# lcmeter.net
KiCad netlist of a schematic drawn in EAGLE
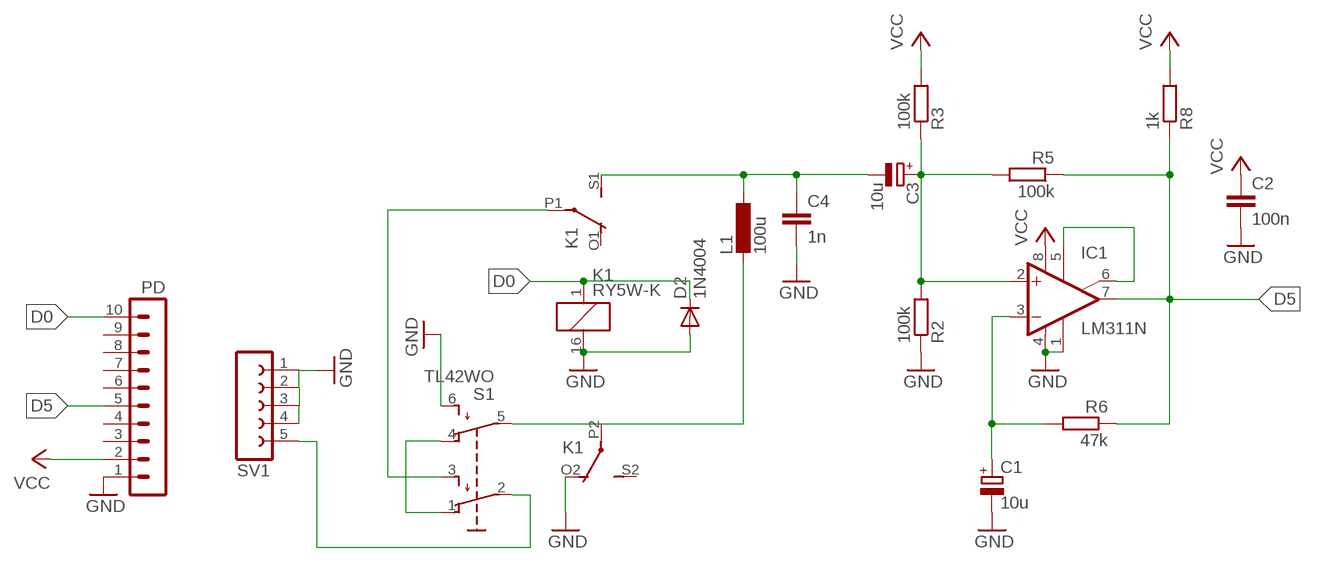
[diagram p0: schematic, sheet 1]

(export (version "E")
  (design (tool "Eeschema 10.0.6"))
  (components
    (comp (ref "C1")
      (value "10u")
      (footprint "eagle-import:E2,5-6")
      (libsource (lib "eagle-import") (part "CPOL-EUE2.5-6"))
    )
    (comp (ref "C2")
      (value "100n")
      (footprint "eagle-import:C025-024X044")
      (libsource (lib "eagle-import") (part "C-EU025-024X044"))
    )
    (comp (ref "C3")
      (value "10u")
      (footprint "eagle-import:TT5D7")
      (libsource (lib "eagle-import") (part "CPOL-EUTT5D7"))
    )
    (comp (ref "C4")
      (value "1n")
      (footprint "eagle-import:C050-025X075")
      (libsource (lib "eagle-import") (part "C-EU050-025X075"))
    )
    (comp (ref "D2")
      (value "1N4004")
      (footprint "eagle-import:DO35-7")
      (libsource (lib "eagle-import") (part "1N4148DO35-7"))
    )
    (comp (ref "IC1")
      (value "LM311N")
      (footprint "eagle-import:DIL08")
      (libsource (lib "eagle-import") (part "LM311N"))
    )
    (comp (ref "K1")
      (value "RY5W-K")
      (footprint "eagle-import:351")
      (libsource (lib "eagle-import") (part "351"))
    )
    (comp (ref "L1")
      (value "100u")
      (footprint "eagle-import:0204_7")
      (libsource (lib "eagle-import") (part "L-EU0204/7"))
    )
    (comp (ref "PD")
      (value "MA10-1W")
      (footprint "eagle-import:MA10-1W")
      (libsource (lib "eagle-import") (part "MA10-1W"))
    )
    (comp (ref "R2")
      (value "100k")
      (footprint "eagle-import:0207_10")
      (libsource (lib "eagle-import") (part "R-EU_0207/10"))
    )
    (comp (ref "R3")
      (value "100k")
      (footprint "eagle-import:0204_7")
      (libsource (lib "eagle-import") (part "R-EU_0204/7"))
    )
    (comp (ref "R5")
      (value "100k")
      (footprint "eagle-import:0204_7")
      (libsource (lib "eagle-import") (part "R-EU_0204/7"))
    )
    (comp (ref "R6")
      (value "47k")
      (footprint "eagle-import:0204_5")
      (libsource (lib "eagle-import") (part "R-EU_0204/5"))
    )
    (comp (ref "R8")
      (value "1k")
      (footprint "eagle-import:0204_7")
      (libsource (lib "eagle-import") (part "R-EU_0204/7"))
    )
    (comp (ref "S1")
      (value "TL42WO")
      (footprint "eagle-import:TL4XWO")
      (libsource (lib "eagle-import") (part "TL42WO"))
    )
    (comp (ref "SV1")
      (value "FE05W")
      (footprint "eagle-import:FE05W")
      (libsource (lib "eagle-import") (part "FE05W"))
    )
  )
  (nets
    (net (code "1") (name "D0") (class "Default")
      (node (ref "D2") (pin "C") (pinfunction "C_C") (pintype "passive"))
      (node (ref "K1") (pin "1") (pinfunction "1_1") (pintype "passive"))
      (node (ref "PD") (pin "10") (pinfunction "10_10") (pintype "passive"))
    )
    (net (code "2") (name "D5") (class "Default")
      (node (ref "IC1") (pin "7") (pinfunction "OUT_7") (pintype "output"))
      (node (ref "PD") (pin "5") (pinfunction "5_5") (pintype "passive"))
      (node (ref "R5") (pin "1") (pinfunction "1_1") (pintype "passive"))
      (node (ref "R6") (pin "1") (pinfunction "1_1") (pintype "passive"))
      (node (ref "R8") (pin "1") (pinfunction "1_1") (pintype "passive"))
    )
    (net (code "3") (name "GND") (class "Default")
      (node (ref "C1") (pin "-") (pinfunction "-_-") (pintype "passive"))
      (node (ref "C2") (pin "2") (pinfunction "2_2") (pintype "passive"))
      (node (ref "C4") (pin "2") (pinfunction "2_2") (pintype "passive"))
      (node (ref "D2") (pin "A") (pinfunction "A_A") (pintype "passive"))
      (node (ref "IC1") (pin "1") (pinfunction "GND_1") (pintype "passive"))
      (node (ref "IC1") (pin "4") (pinfunction "V-_4") (pintype "power_in"))
      (node (ref "K1") (pin "16") (pinfunction "2_16") (pintype "passive"))
      (node (ref "K1") (pin "O2") (pinfunction "O_O2") (pintype "passive"))
      (node (ref "PD") (pin "1") (pinfunction "1_1") (pintype "passive"))
      (node (ref "R2") (pin "1") (pinfunction "1_1") (pintype "passive"))
      (node (ref "S1") (pin "6") (pinfunction "S1_6") (pintype "passive"))
      (node (ref "SV1") (pin "1") (pinfunction "1_1") (pintype "passive"))
      (node (ref "SV1") (pin "2") (pinfunction "2_2") (pintype "passive"))
      (node (ref "SV1") (pin "3") (pinfunction "3_3") (pintype "passive"))
      (node (ref "SV1") (pin "4") (pinfunction "4_4") (pintype "passive"))
    )
    (net (code "4") (name "Net-(IC1-+IN)") (class "Default")
      (node (ref "C3") (pin "+") (pinfunction "+_+") (pintype "passive"))
      (node (ref "IC1") (pin "2") (pinfunction "+IN_2") (pintype "input"))
      (node (ref "R2") (pin "2") (pinfunction "2_2") (pintype "passive"))
      (node (ref "R3") (pin "1") (pinfunction "1_1") (pintype "passive"))
      (node (ref "R5") (pin "2") (pinfunction "2_2") (pintype "passive"))
    )
    (net (code "5") (name "Net-(IC1--IN)") (class "Default")
      (node (ref "C1") (pin "+") (pinfunction "+_+") (pintype "passive"))
      (node (ref "IC1") (pin "3") (pinfunction "-IN_3") (pintype "input"))
      (node (ref "R6") (pin "2") (pinfunction "2_2") (pintype "passive"))
    )
    (net (code "6") (name "Net-(IC1-ON)") (class "Default")
      (node (ref "IC1") (pin "5") (pinfunction "ON_5") (pintype "passive"))
      (node (ref "IC1") (pin "6") (pinfunction "ON/STR_6") (pintype "passive"))
    )
    (net (code "7") (name "Net-(K1B-P)") (class "Default")
      (node (ref "K1") (pin "P1") (pinfunction "P_P1") (pintype "passive"))
      (node (ref "S1") (pin "3") (pinfunction "S_3") (pintype "passive"))
    )
    (net (code "8") (name "Net-(K1B-S)") (class "Default")
      (node (ref "C3") (pin "-") (pinfunction "-_-") (pintype "passive"))
      (node (ref "C4") (pin "1") (pinfunction "1_1") (pintype "passive"))
      (node (ref "K1") (pin "S1") (pinfunction "S_S1") (pintype "passive"))
      (node (ref "L1") (pin "1") (pinfunction "1_1") (pintype "passive"))
    )
    (net (code "9") (name "Net-(K1C-P)") (class "Default")
      (node (ref "K1") (pin "P2") (pinfunction "P_P2") (pintype "passive"))
      (node (ref "L1") (pin "2") (pinfunction "2_2") (pintype "passive"))
      (node (ref "S1") (pin "5") (pinfunction "P1_5") (pintype "passive"))
    )
    (net (code "10") (name "Net-(S1-O)") (class "Default")
      (node (ref "S1") (pin "1") (pinfunction "O_1") (pintype "passive"))
      (node (ref "S1") (pin "4") (pinfunction "O1_4") (pintype "passive"))
    )
    (net (code "11") (name "Net-(S1-P)") (class "Default")
      (node (ref "S1") (pin "2") (pinfunction "P_2") (pintype "passive"))
      (node (ref "SV1") (pin "5") (pinfunction "5_5") (pintype "passive"))
    )
    (net (code "12") (name "VCC") (class "Default")
      (node (ref "C2") (pin "1") (pinfunction "1_1") (pintype "passive"))
      (node (ref "IC1") (pin "8") (pinfunction "V+_8") (pintype "power_in"))
      (node (ref "PD") (pin "2") (pinfunction "2_2") (pintype "passive"))
      (node (ref "R3") (pin "2") (pinfunction "2_2") (pintype "passive"))
      (node (ref "R8") (pin "2") (pinfunction "2_2") (pintype "passive"))
    )
    (net (code "13") (name "unconnected-(K1B-O-PadO1)") (class "Default")
      (node (ref "K1") (pin "O1") (pinfunction "O_O1") (pintype "passive"))
    )
    (net (code "14") (name "unconnected-(K1C-S-PadS2)") (class "Default")
      (node (ref "K1") (pin "S2") (pinfunction "S_S2") (pintype "passive"))
    )
    (net (code "15") (name "unconnected-(PD-Pad3)") (class "Default")
      (node (ref "PD") (pin "3") (pinfunction "3_3") (pintype "passive"))
    )
    (net (code "16") (name "unconnected-(PD-Pad4)") (class "Default")
      (node (ref "PD") (pin "4") (pinfunction "4_4") (pintype "passive"))
    )
    (net (code "17") (name "unconnected-(PD-Pad6)") (class "Default")
      (node (ref "PD") (pin "6") (pinfunction "6_6") (pintype "passive"))
    )
    (net (code "18") (name "unconnected-(PD-Pad7)") (class "Default")
      (node (ref "PD") (pin "7") (pinfunction "7_7") (pintype "passive"))
    )
    (net (code "19") (name "unconnected-(PD-Pad8)") (class "Default")
      (node (ref "PD") (pin "8") (pinfunction "8_8") (pintype "passive"))
    )
    (net (code "20") (name "unconnected-(PD-Pad9)") (class "Default")
      (node (ref "PD") (pin "9") (pinfunction "9_9") (pintype "passive"))
    )
  )
)
